# Peripheral.net
KiCad netlist of a schematic drawn in Altium Designer
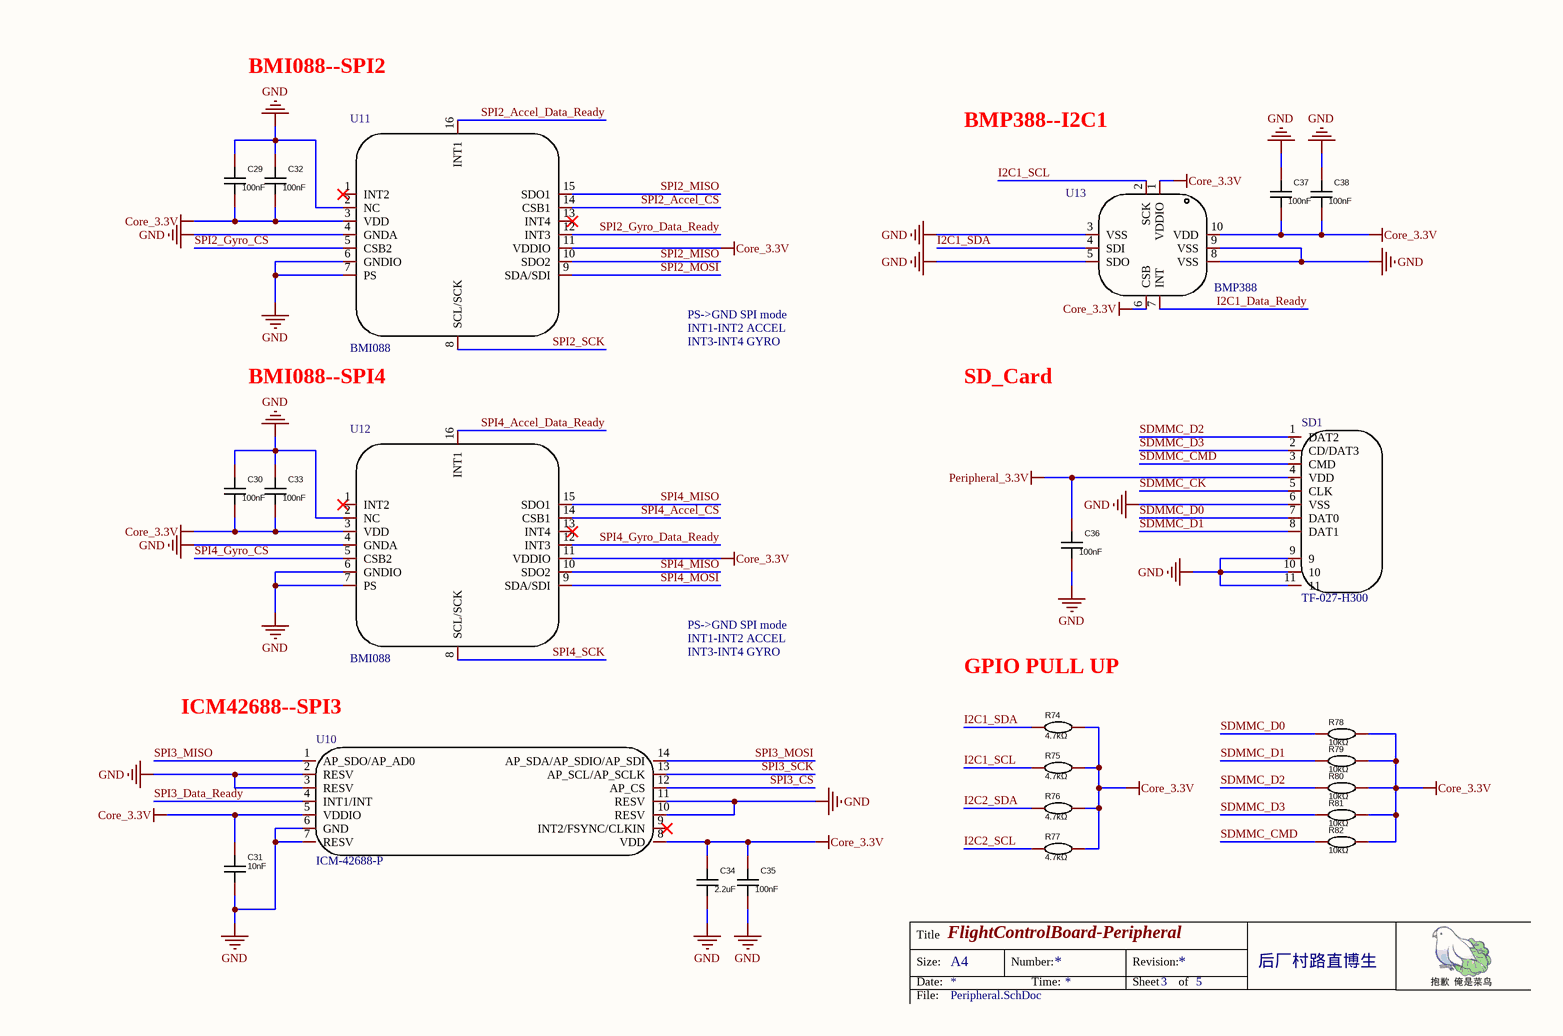
[diagram p0: Peripheral.SchDoc]

(export (version "E")
  (design (tool "Eeschema 10.0.6"))
  (components
    (comp (ref "C29")
      (value "100nF")
      (footprint "C0201")
      (libsource (lib "Capacitor") (part "CC0603KRX7R9BB104"))
    )
    (comp (ref "C30")
      (value "100nF")
      (footprint "C0201")
      (libsource (lib "Capacitor") (part "CC0603KRX7R9BB104"))
    )
    (comp (ref "C31")
      (value "10nF")
      (footprint "C0201")
      (libsource (lib "Capacitor") (part "CC0603KRX7R9BB104"))
    )
    (comp (ref "C32")
      (value "100nF")
      (footprint "C0201")
      (libsource (lib "Capacitor") (part "CC0603KRX7R9BB104"))
    )
    (comp (ref "C33")
      (value "100nF")
      (footprint "C0201")
      (libsource (lib "Capacitor") (part "CC0603KRX7R9BB104"))
    )
    (comp (ref "C34")
      (value "2.2uF")
      (footprint "C0402")
      (libsource (lib "Capacitor") (part "CC0603KRX7R9BB104"))
    )
    (comp (ref "C35")
      (value "100nF")
      (footprint "C0201")
      (libsource (lib "Capacitor") (part "CC0603KRX7R9BB104"))
    )
    (comp (ref "C36")
      (value "100nF")
      (footprint "C0201")
      (libsource (lib "Capacitor") (part "CC0603KRX7R9BB104"))
    )
    (comp (ref "C37")
      (value "100nF")
      (footprint "C0201")
      (libsource (lib "Capacitor") (part "CC0603KRX7R9BB104"))
    )
    (comp (ref "C38")
      (value "100nF")
      (footprint "C0201")
      (libsource (lib "Capacitor") (part "CC0603KRX7R9BB104"))
    )
    (comp (ref "R74")
      (value "4.7kΩ")
      (footprint "R0201")
      (libsource (lib "Resistor") (part "0603WAF1002T5E"))
    )
    (comp (ref "R75")
      (value "4.7kΩ")
      (footprint "R0201")
      (libsource (lib "Resistor") (part "0603WAF1002T5E"))
    )
    (comp (ref "R76")
      (value "4.7kΩ")
      (footprint "R0201")
      (libsource (lib "Resistor") (part "0603WAF1002T5E"))
    )
    (comp (ref "R77")
      (value "4.7kΩ")
      (footprint "R0201")
      (libsource (lib "Resistor") (part "0603WAF1002T5E"))
    )
    (comp (ref "R78") (value "10kΩ") (footprint "R0201") (libsource (lib "Resistor") (part "0603WAF1002T5E")))
    (comp (ref "R79") (value "10kΩ") (footprint "R0201") (libsource (lib "Resistor") (part "0603WAF1002T5E")))
    (comp (ref "R80") (value "10kΩ") (footprint "R0201") (libsource (lib "Resistor") (part "0603WAF1002T5E")))
    (comp (ref "R81") (value "10kΩ") (footprint "R0201") (libsource (lib "Resistor") (part "0603WAF1002T5E")))
    (comp (ref "R82") (value "10kΩ") (footprint "R0201") (libsource (lib "Resistor") (part "0603WAF1002T5E")))
    (comp (ref "SD1")
      (value "TF-027-H300")
      (footprint "TF-SMD_HYCW104-TF08-375B")
      (fields (field (name "MANUFACTURER") "HANBO(汉博)"))
      (libsource (lib "SD-Card") (part "TF-027-H300"))
    )
    (comp (ref "U10")
      (value "ICM-42688-P")
      (footprint "LGA-14_L3.0-W2.5-P0.50-TL")
      (fields (field (name "MANUFACTURER") "TDK InvenSense(应美盛)"))
      (libsource (lib "IMU") (part "ICM-42688-P"))
    )
    (comp (ref "U11")
      (value "BMI088")
      (footprint "LGA-16_L4.5-W3.0-P0.50-BL")
      (fields (field (name "MANUFACTURER") "Bosch(博世)"))
      (libsource (lib "IMU") (part "BMI088"))
    )
    (comp (ref "U12")
      (value "BMI088")
      (footprint "LGA-16_L4.5-W3.0-P0.50-BL")
      (fields (field (name "MANUFACTURER") "Bosch(博世)"))
      (libsource (lib "IMU") (part "BMI088"))
    )
    (comp (ref "U13")
      (value "BMP388")
      (footprint "LGA-10")
      (fields (field (name "MANUFACTURER") "Bosch(博世)"))
      (libsource (lib "Barometer") (part "BMP388"))
    )
  )
  (nets
    (net (code "1") (name "/I2C1_Data_Ready") (class "Default")
      (node (ref "U13") (pin "7") (pinfunction "INT_7") (pintype "passive"))
    )
    (net (code "2") (name "/I2C1_SCL") (class "Default")
      (node (ref "R75") (pin "1") (pinfunction "1_1") (pintype "passive"))
      (node (ref "U13") (pin "2") (pinfunction "SCK_2") (pintype "passive"))
    )
    (net (code "3") (name "/I2C1_SDA") (class "Default")
      (node (ref "R74") (pin "1") (pinfunction "1_1") (pintype "passive"))
      (node (ref "U13") (pin "4") (pinfunction "SDI_4") (pintype "passive"))
    )
    (net (code "4") (name "/I2C2_SCL") (class "Default")
      (node (ref "R77") (pin "1") (pinfunction "1_1") (pintype "passive"))
    )
    (net (code "5") (name "/I2C2_SDA") (class "Default")
      (node (ref "R76") (pin "1") (pinfunction "1_1") (pintype "passive"))
    )
    (net (code "6") (name "/SDMMC_CK") (class "Default")
      (node (ref "SD1") (pin "5") (pinfunction "CLK_5") (pintype "passive"))
    )
    (net (code "7") (name "/SDMMC_CMD") (class "Default")
      (node (ref "R82") (pin "1") (pinfunction "1_1") (pintype "passive"))
      (node (ref "SD1") (pin "3") (pinfunction "CMD_3") (pintype "passive"))
    )
    (net (code "8") (name "/SDMMC_D0") (class "Default")
      (node (ref "R78") (pin "1") (pinfunction "1_1") (pintype "passive"))
      (node (ref "SD1") (pin "7") (pinfunction "DAT0_7") (pintype "passive"))
    )
    (net (code "9") (name "/SDMMC_D1") (class "Default")
      (node (ref "R79") (pin "1") (pinfunction "1_1") (pintype "passive"))
      (node (ref "SD1") (pin "8") (pinfunction "DAT1_8") (pintype "passive"))
    )
    (net (code "10") (name "/SDMMC_D2") (class "Default")
      (node (ref "R80") (pin "1") (pinfunction "1_1") (pintype "passive"))
      (node (ref "SD1") (pin "1") (pinfunction "DAT2_1") (pintype "passive"))
    )
    (net (code "11") (name "/SDMMC_D3") (class "Default")
      (node (ref "R81") (pin "1") (pinfunction "1_1") (pintype "passive"))
      (node (ref "SD1") (pin "2") (pinfunction "CD/DAT3_2") (pintype "passive"))
    )
    (net (code "12") (name "/SPI2_Accel_CS") (class "Default")
      (node (ref "U11") (pin "14") (pinfunction "CSB1_14") (pintype "passive"))
    )
    (net (code "13") (name "/SPI2_Accel_Data_Ready") (class "Default")
      (node (ref "U11") (pin "16") (pinfunction "INT1_16") (pintype "passive"))
    )
    (net (code "14") (name "/SPI2_Gyro_CS") (class "Default")
      (node (ref "U11") (pin "5") (pinfunction "CSB2_5") (pintype "passive"))
    )
    (net (code "15") (name "/SPI2_Gyro_Data_Ready") (class "Default")
      (node (ref "U11") (pin "12") (pinfunction "INT3_12") (pintype "passive"))
    )
    (net (code "16") (name "/SPI2_MISO") (class "Default")
      (node (ref "U11") (pin "10") (pinfunction "SDO2_10") (pintype "passive"))
      (node (ref "U11") (pin "15") (pinfunction "SDO1_15") (pintype "passive"))
    )
    (net (code "17") (name "/SPI2_MOSI") (class "Default")
      (node (ref "U11") (pin "9") (pinfunction "SDA/SDI_9") (pintype "passive"))
    )
    (net (code "18") (name "/SPI2_SCK") (class "Default")
      (node (ref "U11") (pin "8") (pinfunction "SCL/SCK_8") (pintype "passive"))
    )
    (net (code "19") (name "/SPI3_CS") (class "Default")
      (node (ref "U10") (pin "12") (pinfunction "AP_CS_12") (pintype "passive"))
    )
    (net (code "20") (name "/SPI3_Data_Ready") (class "Default")
      (node (ref "U10") (pin "4") (pinfunction "INT1/INT_4") (pintype "passive"))
    )
    (net (code "21") (name "/SPI3_MISO") (class "Default")
      (node (ref "U10") (pin "1") (pinfunction "AP_SDO/AP_AD0_1") (pintype "passive"))
    )
    (net (code "22") (name "/SPI3_MOSI") (class "Default")
      (node (ref "U10") (pin "14") (pinfunction "AP_SDA/AP_SDIO/AP_SDI_14") (pintype "passive"))
    )
    (net (code "23") (name "/SPI3_SCK") (class "Default")
      (node (ref "U10") (pin "13") (pinfunction "AP_SCL/AP_SCLK_13") (pintype "passive"))
    )
    (net (code "24") (name "/SPI4_Accel_CS") (class "Default")
      (node (ref "U12") (pin "14") (pinfunction "CSB1_14") (pintype "passive"))
    )
    (net (code "25") (name "/SPI4_Accel_Data_Ready") (class "Default")
      (node (ref "U12") (pin "16") (pinfunction "INT1_16") (pintype "passive"))
    )
    (net (code "26") (name "/SPI4_Gyro_CS") (class "Default")
      (node (ref "U12") (pin "5") (pinfunction "CSB2_5") (pintype "passive"))
    )
    (net (code "27") (name "/SPI4_Gyro_Data_Ready") (class "Default")
      (node (ref "U12") (pin "12") (pinfunction "INT3_12") (pintype "passive"))
    )
    (net (code "28") (name "/SPI4_MISO") (class "Default")
      (node (ref "U12") (pin "10") (pinfunction "SDO2_10") (pintype "passive"))
      (node (ref "U12") (pin "15") (pinfunction "SDO1_15") (pintype "passive"))
    )
    (net (code "29") (name "/SPI4_MOSI") (class "Default")
      (node (ref "U12") (pin "9") (pinfunction "SDA/SDI_9") (pintype "passive"))
    )
    (net (code "30") (name "/SPI4_SCK") (class "Default")
      (node (ref "U12") (pin "8") (pinfunction "SCL/SCK_8") (pintype "passive"))
    )
    (net (code "31") (name "Core_3.3V") (class "Default")
      (node (ref "C29") (pin "1") (pinfunction "1_1") (pintype "passive"))
      (node (ref "C30") (pin "1") (pinfunction "1_1") (pintype "passive"))
      (node (ref "C31") (pin "1") (pinfunction "1_1") (pintype "passive"))
      (node (ref "C32") (pin "1") (pinfunction "1_1") (pintype "passive"))
      (node (ref "C33") (pin "1") (pinfunction "1_1") (pintype "passive"))
      (node (ref "C34") (pin "2") (pinfunction "2_2") (pintype "passive"))
      (node (ref "C35") (pin "2") (pinfunction "2_2") (pintype "passive"))
      (node (ref "C37") (pin "1") (pinfunction "1_1") (pintype "passive"))
      (node (ref "C38") (pin "1") (pinfunction "1_1") (pintype "passive"))
      (node (ref "R74") (pin "2") (pinfunction "2_2") (pintype "passive"))
      (node (ref "R75") (pin "2") (pinfunction "2_2") (pintype "passive"))
      (node (ref "R76") (pin "2") (pinfunction "2_2") (pintype "passive"))
      (node (ref "R77") (pin "2") (pinfunction "2_2") (pintype "passive"))
      (node (ref "R78") (pin "2") (pinfunction "2_2") (pintype "passive"))
      (node (ref "R79") (pin "2") (pinfunction "2_2") (pintype "passive"))
      (node (ref "R80") (pin "2") (pinfunction "2_2") (pintype "passive"))
      (node (ref "R81") (pin "2") (pinfunction "2_2") (pintype "passive"))
      (node (ref "R82") (pin "2") (pinfunction "2_2") (pintype "passive"))
      (node (ref "U10") (pin "5") (pinfunction "VDDIO_5") (pintype "passive"))
      (node (ref "U10") (pin "8") (pinfunction "VDD_8") (pintype "passive"))
      (node (ref "U11") (pin "11") (pinfunction "VDDIO_11") (pintype "passive"))
      (node (ref "U11") (pin "3") (pinfunction "VDD_3") (pintype "passive"))
      (node (ref "U12") (pin "11") (pinfunction "VDDIO_11") (pintype "passive"))
      (node (ref "U12") (pin "3") (pinfunction "VDD_3") (pintype "passive"))
      (node (ref "U13") (pin "1") (pinfunction "VDDIO_1") (pintype "passive"))
      (node (ref "U13") (pin "10") (pinfunction "VDD_10") (pintype "passive"))
      (node (ref "U13") (pin "6") (pinfunction "CSB_6") (pintype "passive"))
    )
    (net (code "32") (name "GND") (class "Default")
      (node (ref "C29") (pin "2") (pinfunction "2_2") (pintype "passive"))
      (node (ref "C30") (pin "2") (pinfunction "2_2") (pintype "passive"))
      (node (ref "C31") (pin "2") (pinfunction "2_2") (pintype "passive"))
      (node (ref "C32") (pin "2") (pinfunction "2_2") (pintype "passive"))
      (node (ref "C33") (pin "2") (pinfunction "2_2") (pintype "passive"))
      (node (ref "C34") (pin "1") (pinfunction "1_1") (pintype "passive"))
      (node (ref "C35") (pin "1") (pinfunction "1_1") (pintype "passive"))
      (node (ref "C36") (pin "1") (pinfunction "1_1") (pintype "passive"))
      (node (ref "C37") (pin "2") (pinfunction "2_2") (pintype "passive"))
      (node (ref "C38") (pin "2") (pinfunction "2_2") (pintype "passive"))
      (node (ref "SD1") (pin "10") (pinfunction "10_10") (pintype "passive"))
      (node (ref "SD1") (pin "11") (pinfunction "11_11") (pintype "passive"))
      (node (ref "SD1") (pin "6") (pinfunction "VSS_6") (pintype "passive"))
      (node (ref "SD1") (pin "9") (pinfunction "9_9") (pintype "passive"))
      (node (ref "U10") (pin "10") (pinfunction "RESV_10") (pintype "passive"))
      (node (ref "U10") (pin "11") (pinfunction "RESV_11") (pintype "passive"))
      (node (ref "U10") (pin "2") (pinfunction "RESV_2") (pintype "passive"))
      (node (ref "U10") (pin "3") (pinfunction "RESV_3") (pintype "passive"))
      (node (ref "U10") (pin "6") (pinfunction "GND_6") (pintype "passive"))
      (node (ref "U10") (pin "7") (pinfunction "RESV_7") (pintype "passive"))
      (node (ref "U11") (pin "2") (pinfunction "NC_2") (pintype "passive"))
      (node (ref "U11") (pin "4") (pinfunction "GNDA_4") (pintype "passive"))
      (node (ref "U11") (pin "6") (pinfunction "GNDIO_6") (pintype "passive"))
      (node (ref "U11") (pin "7") (pinfunction "PS_7") (pintype "passive"))
      (node (ref "U12") (pin "2") (pinfunction "NC_2") (pintype "passive"))
      (node (ref "U12") (pin "4") (pinfunction "GNDA_4") (pintype "passive"))
      (node (ref "U12") (pin "6") (pinfunction "GNDIO_6") (pintype "passive"))
      (node (ref "U12") (pin "7") (pinfunction "PS_7") (pintype "passive"))
      (node (ref "U13") (pin "3") (pinfunction "VSS_3") (pintype "passive"))
      (node (ref "U13") (pin "5") (pinfunction "SDO_5") (pintype "passive"))
      (node (ref "U13") (pin "8") (pinfunction "VSS_8") (pintype "passive"))
      (node (ref "U13") (pin "9") (pinfunction "VSS_9") (pintype "passive"))
    )
    (net (code "33") (name "Peripheral_3.3V") (class "Default")
      (node (ref "C36") (pin "2") (pinfunction "2_2") (pintype "passive"))
      (node (ref "SD1") (pin "4") (pinfunction "VDD_4") (pintype "passive"))
    )
    (net (code "34") (name "unconnected-(U10-INT2{slash}FSYNC{slash}CLKIN-Pad9)") (class "Default")
      (node (ref "U10") (pin "9") (pinfunction "INT2/FSYNC/CLKIN_9") (pintype "passive+no_connect"))
    )
    (net (code "35") (name "unconnected-(U11-INT2-Pad1)") (class "Default")
      (node (ref "U11") (pin "1") (pinfunction "INT2_1") (pintype "passive+no_connect"))
    )
    (net (code "36") (name "unconnected-(U11-INT4-Pad13)") (class "Default")
      (node (ref "U11") (pin "13") (pinfunction "INT4_13") (pintype "passive+no_connect"))
    )
    (net (code "37") (name "unconnected-(U12-INT2-Pad1)") (class "Default")
      (node (ref "U12") (pin "1") (pinfunction "INT2_1") (pintype "passive+no_connect"))
    )
    (net (code "38") (name "unconnected-(U12-INT4-Pad13)") (class "Default")
      (node (ref "U12") (pin "13") (pinfunction "INT4_13") (pintype "passive+no_connect"))
    )
  )
)
